# MCU_Connectors.net
KiCad netlist of a schematic drawn in Altium Designer
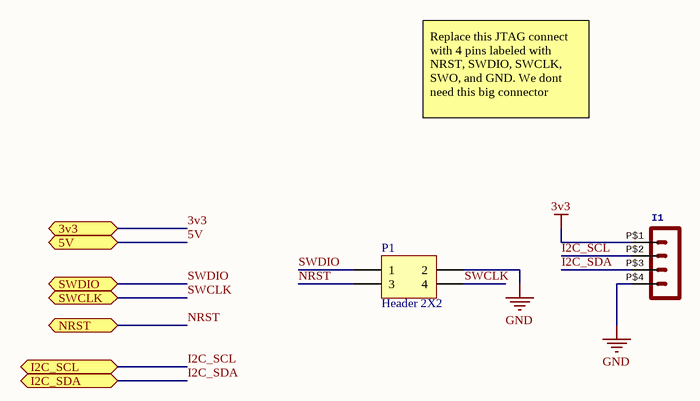
[diagram p0: MCU_Connectors.SchDoc]

(export (version "E")
  (design (tool "Eeschema 10.0.6"))
  (components
    (comp (ref "I1")
      (value "Molex - Micro-Fit 3.0 Series connector,  3.00mm (0.118\") pitch header, 4 positions.")
      (footprint "44914-0401")
      (libsource (lib "Molex Microfit") (part "HEADER_POS4_?44914-0401"))
    )
    (comp (ref "P1")
      (value "Header 2X2")
      (footprint "HDR2X2")
      (description "Header, 2-Pin, Dual row")
      (fields (field (name "PUBLISHER") "Altium Limited"))
      (libsource (lib "Miscellaneous Connectors") (part "Header 2X2"))
    )
  )
  (nets
    (net (code "2") (name "/I2C_SCL") (class "Default")
      (node (ref "I1") (pin "P$2") (pinfunction "2_P$2") (pintype "passive"))
    )
    (net (code "3") (name "/I2C_SDA") (class "Default")
      (node (ref "I1") (pin "P$3") (pinfunction "3_P$3") (pintype "passive"))
    )
    (net (code "4") (name "/NRST") (class "Default")
      (node (ref "P1") (pin "3") (pinfunction "3_3") (pintype "passive"))
    )
    (net (code "5") (name "/SWCLK") (class "Default")
      (node (ref "P1") (pin "4") (pinfunction "4_4") (pintype "passive"))
    )
    (net (code "6") (name "/SWDIO") (class "Default")
      (node (ref "P1") (pin "1") (pinfunction "1_1") (pintype "passive"))
    )
    (net (code "7") (name "3v3") (class "Default")
      (node (ref "I1") (pin "P$1") (pinfunction "1_P$1") (pintype "passive"))
    )
    (net (code "8") (name "GND") (class "Default")
      (node (ref "I1") (pin "P$4") (pinfunction "4_P$4") (pintype "passive"))
      (node (ref "P1") (pin "2") (pinfunction "2_2") (pintype "passive"))
    )
  )
)
